# USB_UART_BRIDGE.net
KiCad netlist of a schematic drawn in Altium Designer
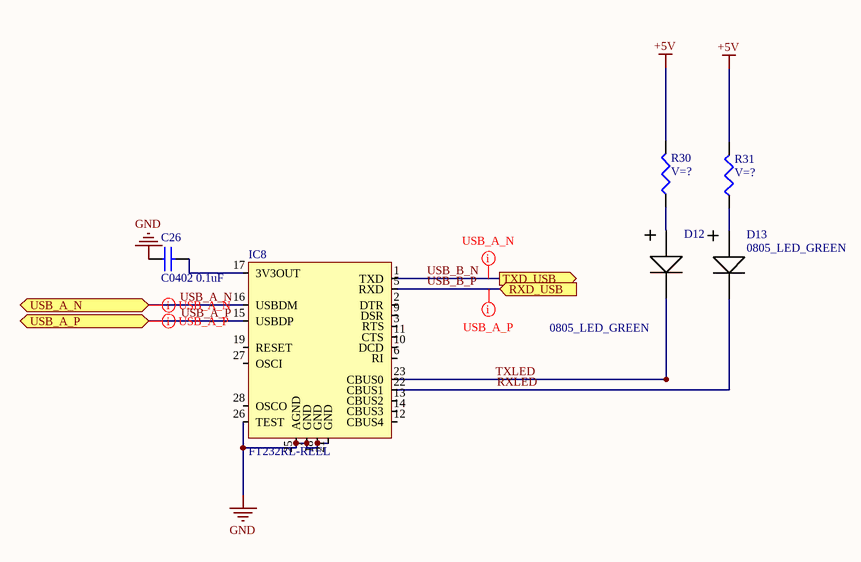
[diagram p0: USB_UART_BRIDGE.SchDoc]

(export (version "E")
  (design (tool "Eeschema 10.0.6"))
  (components
    (comp (ref "C26")
      (value "C0402 0.1uF")
      (footprint "C0402")
      (description "CAP CER 0.1uF 16V X7R 0402 / SAMSUNG")
      (libsource (lib "COOP4403_BerkantAY") (part "C0402 0.1uF"))
    )
    (comp (ref "D12")
      (value "0805_LED_GREEN")
      (footprint "0805LED_GREEN")
      (description "LGR971-KN OSRAM")
      (libsource (lib "COOP4403_BerkantAY") (part "0805_LED_GREEN"))
    )
    (comp (ref "D13")
      (value "0805_LED_GREEN")
      (footprint "0805LED_GREEN")
      (description "LGR971-KN OSRAM")
      (libsource (lib "COOP4403_BerkantAY") (part "0805_LED_GREEN"))
    )
    (comp (ref "IC8")
      (value "FT232RL-REEL")
      (footprint "SSOP28")
      (description "IC USB FS SERIAL UART 28-SSOP")
      (libsource (lib "COOP4403_BerkantAY") (part "FT232RL-REEL"))
    )
    (comp (ref "R30")
      (value "V=?")
      (footprint "r0402")
      (description "RESISTOR")
      (libsource (lib "COOP4403_BerkantAY") (part "R0402"))
    )
    (comp (ref "R31")
      (value "V=?")
      (footprint "r0402")
      (description "RESISTOR")
      (libsource (lib "COOP4403_BerkantAY") (part "R0402"))
    )
  )
  (nets
    (net (code "1") (name "+5V") (class "Default")
      (node (ref "R30") (pin "2") (pinfunction "2_2") (pintype "passive"))
      (node (ref "R31") (pin "2") (pinfunction "2_2") (pintype "passive"))
    )
    (net (code "2") (name "/RXLED") (class "Default")
      (node (ref "D13") (pin "1") (pinfunction "1_1") (pintype "passive"))
      (node (ref "IC8") (pin "22") (pinfunction "CBUS1_22") (pintype "passive"))
    )
    (net (code "3") (name "/TXLED") (class "Default")
      (node (ref "D12") (pin "1") (pinfunction "1_1") (pintype "passive"))
      (node (ref "IC8") (pin "23") (pinfunction "CBUS0_23") (pintype "passive"))
    )
    (net (code "4") (name "/USB_A_N") (class "Default")
      (node (ref "IC8") (pin "16") (pinfunction "USBDM_16") (pintype "passive"))
    )
    (net (code "5") (name "/USB_A_P") (class "Default")
      (node (ref "IC8") (pin "15") (pinfunction "USBDP_15") (pintype "passive"))
    )
    (net (code "6") (name "/USB_B_N") (class "Default")
      (node (ref "IC8") (pin "1") (pinfunction "TXD_1") (pintype "passive"))
    )
    (net (code "7") (name "/USB_B_P") (class "Default")
      (node (ref "IC8") (pin "5") (pinfunction "RXD_5") (pintype "passive"))
    )
    (net (code "8") (name "GND") (class "Default")
      (node (ref "C26") (pin "1") (pinfunction "1_1") (pintype "passive"))
      (node (ref "IC8") (pin "18") (pinfunction "GND_18") (pintype "passive"))
      (node (ref "IC8") (pin "21") (pinfunction "GND_21") (pintype "passive"))
      (node (ref "IC8") (pin "25") (pinfunction "AGND_25") (pintype "passive"))
      (node (ref "IC8") (pin "26") (pinfunction "TEST_26") (pintype "passive"))
      (node (ref "IC8") (pin "7") (pinfunction "GND_7") (pintype "passive"))
    )
    (net (code "9") (name "Net-(D12-Pad2)") (class "Default")
      (node (ref "D12") (pin "2") (pinfunction "2_2") (pintype "passive"))
      (node (ref "R30") (pin "1") (pinfunction "1_1") (pintype "passive"))
    )
    (net (code "10") (name "Net-(D13-Pad2)") (class "Default")
      (node (ref "D13") (pin "2") (pinfunction "2_2") (pintype "passive"))
      (node (ref "R31") (pin "1") (pinfunction "1_1") (pintype "passive"))
    )
    (net (code "11") (name "Net-(IC8-3V3OUT)") (class "Default")
      (node (ref "C26") (pin "2") (pinfunction "2_2") (pintype "passive"))
      (node (ref "IC8") (pin "17") (pinfunction "3V3OUT_17") (pintype "passive"))
    )
    (net (code "12") (name "unconnected-(IC8-CBUS2-Pad13)") (class "Default")
      (node (ref "IC8") (pin "13") (pinfunction "CBUS2_13") (pintype "passive"))
    )
    (net (code "13") (name "unconnected-(IC8-CBUS3-Pad14)") (class "Default")
      (node (ref "IC8") (pin "14") (pinfunction "CBUS3_14") (pintype "passive"))
    )
    (net (code "14") (name "unconnected-(IC8-CBUS4-Pad12)") (class "Default")
      (node (ref "IC8") (pin "12") (pinfunction "CBUS4_12") (pintype "passive"))
    )
    (net (code "15") (name "unconnected-(IC8-CTS-Pad11)") (class "Default")
      (node (ref "IC8") (pin "11") (pinfunction "CTS_11") (pintype "passive"))
    )
    (net (code "16") (name "unconnected-(IC8-DCD-Pad10)") (class "Default")
      (node (ref "IC8") (pin "10") (pinfunction "DCD_10") (pintype "passive"))
    )
    (net (code "17") (name "unconnected-(IC8-DSR-Pad9)") (class "Default")
      (node (ref "IC8") (pin "9") (pinfunction "DSR_9") (pintype "passive"))
    )
    (net (code "18") (name "unconnected-(IC8-DTR-Pad2)") (class "Default")
      (node (ref "IC8") (pin "2") (pinfunction "DTR_2") (pintype "passive"))
    )
    (net (code "19") (name "unconnected-(IC8-OSCI-Pad27)") (class "Default")
      (node (ref "IC8") (pin "27") (pinfunction "OSCI_27") (pintype "passive"))
    )
    (net (code "20") (name "unconnected-(IC8-OSCO-Pad28)") (class "Default")
      (node (ref "IC8") (pin "28") (pinfunction "OSCO_28") (pintype "passive"))
    )
    (net (code "21") (name "unconnected-(IC8-RESET-Pad19)") (class "Default")
      (node (ref "IC8") (pin "19") (pinfunction "RESET_19") (pintype "passive"))
    )
    (net (code "22") (name "unconnected-(IC8-RI-Pad6)") (class "Default")
      (node (ref "IC8") (pin "6") (pinfunction "RI_6") (pintype "passive"))
    )
    (net (code "23") (name "unconnected-(IC8-RTS-Pad3)") (class "Default")
      (node (ref "IC8") (pin "3") (pinfunction "RTS_3") (pintype "passive"))
    )
  )
)
